# KnightOfTone.net
KiCad netlist of a schematic drawn in EAGLE
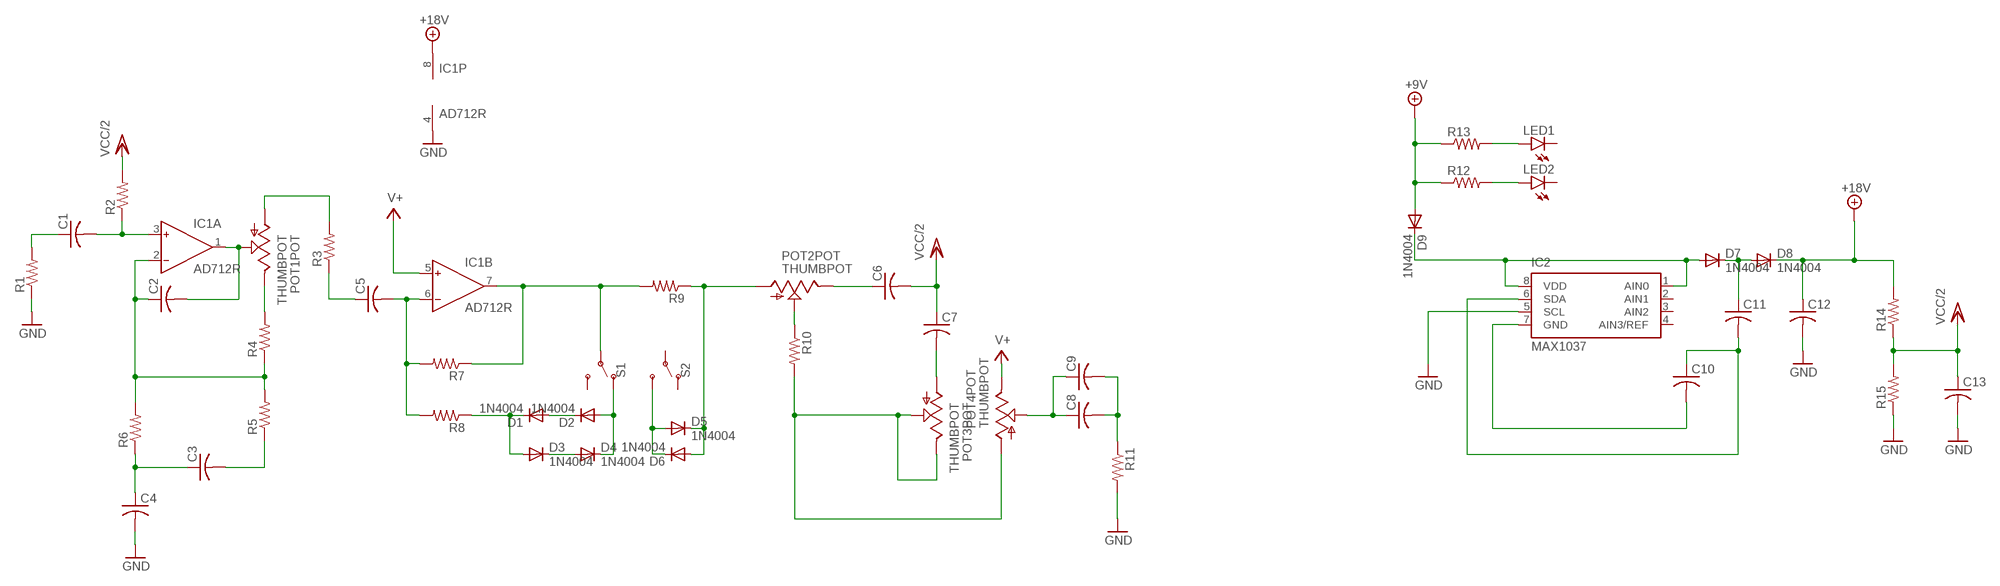
[diagram p0: schematic, sheet 1]

(export (version "E")
  (design (tool "Eeschema 10.0.6"))
  (components
    (comp (ref "C1")
      (value "C-USC0603")
      (footprint "eagle-import:C0603")
      (libsource (lib "eagle-import") (part "C-USC0603"))
    )
    (comp (ref "C2")
      (value "C-USC0603")
      (footprint "eagle-import:C0603")
      (libsource (lib "eagle-import") (part "C-USC0603"))
    )
    (comp (ref "C3")
      (value "C-USC0603")
      (footprint "eagle-import:C0603")
      (libsource (lib "eagle-import") (part "C-USC0603"))
    )
    (comp (ref "C4")
      (value "C-USC0603")
      (footprint "eagle-import:C0603")
      (libsource (lib "eagle-import") (part "C-USC0603"))
    )
    (comp (ref "C5")
      (value "C-USC0603")
      (footprint "eagle-import:C0603")
      (libsource (lib "eagle-import") (part "C-USC0603"))
    )
    (comp (ref "C6")
      (value "C-USC0603")
      (footprint "eagle-import:C0603")
      (libsource (lib "eagle-import") (part "C-USC0603"))
    )
    (comp (ref "C7")
      (value "C-USC0603")
      (footprint "eagle-import:C0603")
      (libsource (lib "eagle-import") (part "C-USC0603"))
    )
    (comp (ref "C8")
      (value "C-USC0603")
      (footprint "eagle-import:C0603")
      (libsource (lib "eagle-import") (part "C-USC0603"))
    )
    (comp (ref "C9")
      (value "C-USC0603")
      (footprint "eagle-import:C0603")
      (libsource (lib "eagle-import") (part "C-USC0603"))
    )
    (comp (ref "C10")
      (value "C-USC0603")
      (footprint "eagle-import:C0603")
      (libsource (lib "eagle-import") (part "C-USC0603"))
    )
    (comp (ref "C11")
      (value "C-USC0603")
      (footprint "eagle-import:C0603")
      (libsource (lib "eagle-import") (part "C-USC0603"))
    )
    (comp (ref "C12")
      (value "C-USC0603")
      (footprint "eagle-import:C0603")
      (libsource (lib "eagle-import") (part "C-USC0603"))
    )
    (comp (ref "C13")
      (value "C-USC0603")
      (footprint "eagle-import:C0603")
      (libsource (lib "eagle-import") (part "C-USC0603"))
    )
    (comp (ref "D1")
      (value "1N4004")
      (footprint "eagle-import:DO41-10")
      (libsource (lib "eagle-import") (part "1N4004"))
    )
    (comp (ref "D2")
      (value "1N4004")
      (footprint "eagle-import:DO41-10")
      (libsource (lib "eagle-import") (part "1N4004"))
    )
    (comp (ref "D3")
      (value "1N4004")
      (footprint "eagle-import:DO41-10")
      (libsource (lib "eagle-import") (part "1N4004"))
    )
    (comp (ref "D4")
      (value "1N4004")
      (footprint "eagle-import:DO41-10")
      (libsource (lib "eagle-import") (part "1N4004"))
    )
    (comp (ref "D5")
      (value "1N4004")
      (footprint "eagle-import:DO41-10")
      (libsource (lib "eagle-import") (part "1N4004"))
    )
    (comp (ref "D6")
      (value "1N4004")
      (footprint "eagle-import:DO41-10")
      (libsource (lib "eagle-import") (part "1N4004"))
    )
    (comp (ref "D7")
      (value "1N4004")
      (footprint "eagle-import:DO41-10")
      (libsource (lib "eagle-import") (part "1N4004"))
    )
    (comp (ref "D8")
      (value "1N4004")
      (footprint "eagle-import:DO41-10")
      (libsource (lib "eagle-import") (part "1N4004"))
    )
    (comp (ref "D9")
      (value "1N4004")
      (footprint "eagle-import:DO41-10")
      (libsource (lib "eagle-import") (part "1N4004"))
    )
    (comp (ref "IC1")
      (value "AD712R")
      (footprint "eagle-import:SO8")
      (fields (field (name "MF") "ALTERA CORPORATION") (field (name "MPN") "AD712KRZ"))
      (libsource (lib "eagle-import") (part "AD712R"))
    )
    (comp (ref "IC2")
      (value "MAX1037")
      (footprint "eagle-import:SOT23-8L")
      (fields (field (name "MF") "MAXIM") (field (name "MPN") "MAX1037EKA+T"))
      (libsource (lib "eagle-import") (part "MAX1037"))
    )
    (comp (ref "LED1")
      (value "LED3MM")
      (footprint "eagle-import:LED3MM")
      (libsource (lib "eagle-import") (part "LED3MM"))
    )
    (comp (ref "LED2")
      (value "LED3MM")
      (footprint "eagle-import:LED3MM")
      (libsource (lib "eagle-import") (part "LED3MM"))
    )
    (comp (ref "POT1")
      (value "THUMBPOT")
      (footprint "eagle-import:THUMBWHEEL")
      (libsource (lib "eagle-import") (part "THUMBPOT"))
    )
    (comp (ref "POT2")
      (value "THUMBPOT")
      (footprint "eagle-import:THUMBWHEEL")
      (libsource (lib "eagle-import") (part "THUMBPOT"))
    )
    (comp (ref "POT3")
      (value "THUMBPOT")
      (footprint "eagle-import:THUMBWHEEL")
      (libsource (lib "eagle-import") (part "THUMBPOT"))
    )
    (comp (ref "POT4")
      (value "THUMBPOT")
      (footprint "eagle-import:THUMBWHEEL")
      (libsource (lib "eagle-import") (part "THUMBPOT"))
    )
    (comp (ref "R1")
      (value "R-US_R0603")
      (footprint "eagle-import:R0603")
      (libsource (lib "eagle-import") (part "R-US_R0603"))
    )
    (comp (ref "R2")
      (value "R-US_R0603")
      (footprint "eagle-import:R0603")
      (libsource (lib "eagle-import") (part "R-US_R0603"))
    )
    (comp (ref "R3")
      (value "R-US_R0603")
      (footprint "eagle-import:R0603")
      (libsource (lib "eagle-import") (part "R-US_R0603"))
    )
    (comp (ref "R4")
      (value "R-US_R0603")
      (footprint "eagle-import:R0603")
      (libsource (lib "eagle-import") (part "R-US_R0603"))
    )
    (comp (ref "R5")
      (value "R-US_R0603")
      (footprint "eagle-import:R0603")
      (libsource (lib "eagle-import") (part "R-US_R0603"))
    )
    (comp (ref "R6")
      (value "R-US_R0603")
      (footprint "eagle-import:R0603")
      (libsource (lib "eagle-import") (part "R-US_R0603"))
    )
    (comp (ref "R7")
      (value "R-US_R0603")
      (footprint "eagle-import:R0603")
      (libsource (lib "eagle-import") (part "R-US_R0603"))
    )
    (comp (ref "R8")
      (value "R-US_R0603")
      (footprint "eagle-import:R0603")
      (libsource (lib "eagle-import") (part "R-US_R0603"))
    )
    (comp (ref "R9")
      (value "R-US_R0603")
      (footprint "eagle-import:R0603")
      (libsource (lib "eagle-import") (part "R-US_R0603"))
    )
    (comp (ref "R10")
      (value "R-US_R0603")
      (footprint "eagle-import:R0603")
      (libsource (lib "eagle-import") (part "R-US_R0603"))
    )
    (comp (ref "R11")
      (value "R-US_R0603")
      (footprint "eagle-import:R0603")
      (libsource (lib "eagle-import") (part "R-US_R0603"))
    )
    (comp (ref "R12")
      (value "R-US_R0603")
      (footprint "eagle-import:R0603")
      (libsource (lib "eagle-import") (part "R-US_R0603"))
    )
    (comp (ref "R13")
      (value "R-US_R0603")
      (footprint "eagle-import:R0603")
      (libsource (lib "eagle-import") (part "R-US_R0603"))
    )
    (comp (ref "R14")
      (value "R-US_R0603")
      (footprint "eagle-import:R0603")
      (libsource (lib "eagle-import") (part "R-US_R0603"))
    )
    (comp (ref "R15")
      (value "R-US_R0603")
      (footprint "eagle-import:R0603")
      (libsource (lib "eagle-import") (part "R-US_R0603"))
    )
    (comp (ref "S1")
      (value "SWITCH-SPDT-PTH-11.6X4.0MM")
      (footprint "eagle-import:SWITCH_SPDT_PTH_11.6X4.0MM")
      (libsource (lib "eagle-import") (part "SWITCH-SPDT-PTH-11.6X4.0MM"))
    )
    (comp (ref "S2")
      (value "SWITCH-SPDT-PTH-11.6X4.0MM")
      (footprint "eagle-import:SWITCH_SPDT_PTH_11.6X4.0MM")
      (libsource (lib "eagle-import") (part "SWITCH-SPDT-PTH-11.6X4.0MM"))
    )
  )
  (nets
    (net (code "1") (name "+9V") (class "Default")
      (node (ref "D9") (pin "A") (pinfunction "A_A") (pintype "passive"))
      (node (ref "R12") (pin "1") (pinfunction "1_1") (pintype "passive"))
      (node (ref "R13") (pin "1") (pinfunction "1_1") (pintype "passive"))
    )
    (net (code "2") (name "+18V") (class "Default")
      (node (ref "C12") (pin "1") (pinfunction "1_1") (pintype "passive"))
      (node (ref "D8") (pin "C") (pinfunction "C_C") (pintype "passive"))
      (node (ref "IC1") (pin "8") (pinfunction "V+_8") (pintype "power_in"))
      (node (ref "R14") (pin "2") (pinfunction "2_2") (pintype "passive"))
    )
    (net (code "3") (name "GND") (class "Default")
      (node (ref "C12") (pin "2") (pinfunction "2_2") (pintype "passive"))
      (node (ref "C13") (pin "2") (pinfunction "2_2") (pintype "passive"))
      (node (ref "C4") (pin "2") (pinfunction "2_2") (pintype "passive"))
      (node (ref "IC1") (pin "4") (pinfunction "V-_4") (pintype "power_in"))
      (node (ref "IC2") (pin "5") (pinfunction "SCL_5") (pintype "input"))
      (node (ref "R1") (pin "1") (pinfunction "1_1") (pintype "passive"))
      (node (ref "R11") (pin "2") (pinfunction "2_2") (pintype "passive"))
      (node (ref "R15") (pin "1") (pinfunction "1_1") (pintype "passive"))
    )
    (net (code "4") (name "Net-(C1-Pad1)") (class "Default")
      (node (ref "C1") (pin "1") (pinfunction "1_1") (pintype "passive"))
      (node (ref "R1") (pin "2") (pinfunction "2_2") (pintype "passive"))
    )
    (net (code "5") (name "Net-(C3-Pad1)") (class "Default")
      (node (ref "C3") (pin "1") (pinfunction "1_1") (pintype "passive"))
      (node (ref "C4") (pin "1") (pinfunction "1_1") (pintype "passive"))
      (node (ref "R6") (pin "1") (pinfunction "1_1") (pintype "passive"))
    )
    (net (code "6") (name "Net-(C3-Pad2)") (class "Default")
      (node (ref "C3") (pin "2") (pinfunction "2_2") (pintype "passive"))
      (node (ref "R5") (pin "1") (pinfunction "1_1") (pintype "passive"))
    )
    (net (code "7") (name "Net-(C5-Pad1)") (class "Default")
      (node (ref "C5") (pin "1") (pinfunction "1_1") (pintype "passive"))
      (node (ref "R3") (pin "1") (pinfunction "1_1") (pintype "passive"))
    )
    (net (code "8") (name "Net-(C8-Pad2)") (class "Default")
      (node (ref "C8") (pin "2") (pinfunction "2_2") (pintype "passive"))
      (node (ref "C9") (pin "2") (pinfunction "2_2") (pintype "passive"))
      (node (ref "R11") (pin "1") (pinfunction "1_1") (pintype "passive"))
    )
    (net (code "9") (name "Net-(C11-Pad1)") (class "Default")
      (node (ref "C11") (pin "1") (pinfunction "1_1") (pintype "passive"))
      (node (ref "D7") (pin "C") (pinfunction "C_C") (pintype "passive"))
      (node (ref "D8") (pin "A") (pinfunction "A_A") (pintype "passive"))
    )
    (net (code "10") (name "Net-(D1-PadA)") (class "Default")
      (node (ref "D1") (pin "A") (pinfunction "A_A") (pintype "passive"))
      (node (ref "D2") (pin "C") (pinfunction "C_C") (pintype "passive"))
    )
    (net (code "11") (name "Net-(D1-PadC)") (class "Default")
      (node (ref "D1") (pin "C") (pinfunction "C_C") (pintype "passive"))
      (node (ref "D3") (pin "A") (pinfunction "A_A") (pintype "passive"))
      (node (ref "R8") (pin "1") (pinfunction "1_1") (pintype "passive"))
    )
    (net (code "12") (name "Net-(D3-PadC)") (class "Default")
      (node (ref "D3") (pin "C") (pinfunction "C_C") (pintype "passive"))
      (node (ref "D4") (pin "A") (pinfunction "A_A") (pintype "passive"))
    )
    (net (code "13") (name "Net-(IC1A-IN+)") (class "Default")
      (node (ref "C1") (pin "2") (pinfunction "2_2") (pintype "passive"))
      (node (ref "IC1") (pin "3") (pinfunction "IN+_3") (pintype "input"))
      (node (ref "R2") (pin "1") (pinfunction "1_1") (pintype "passive"))
    )
    (net (code "14") (name "Net-(IC1A-IN-)") (class "Default")
      (node (ref "C2") (pin "1") (pinfunction "1_1") (pintype "passive"))
      (node (ref "IC1") (pin "2") (pinfunction "IN-_2") (pintype "input"))
      (node (ref "R4") (pin "1") (pinfunction "1_1") (pintype "passive"))
      (node (ref "R5") (pin "2") (pinfunction "2_2") (pintype "passive"))
      (node (ref "R6") (pin "2") (pinfunction "2_2") (pintype "passive"))
    )
    (net (code "15") (name "Net-(IC1A-OUT)") (class "Default")
      (node (ref "C2") (pin "2") (pinfunction "2_2") (pintype "passive"))
      (node (ref "IC1") (pin "1") (pinfunction "OUT_1") (pintype "output"))
      (node (ref "POT1") (pin "2") (pinfunction "S_2") (pintype "passive"))
    )
    (net (code "16") (name "Net-(IC1B-IN-)") (class "Default")
      (node (ref "C5") (pin "2") (pinfunction "2_2") (pintype "passive"))
      (node (ref "IC1") (pin "6") (pinfunction "IN-_6") (pintype "input"))
      (node (ref "R7") (pin "2") (pinfunction "2_2") (pintype "passive"))
      (node (ref "R8") (pin "2") (pinfunction "2_2") (pintype "passive"))
    )
    (net (code "17") (name "Net-(IC1B-OUT)") (class "Default")
      (node (ref "IC1") (pin "7") (pinfunction "OUT_7") (pintype "output"))
      (node (ref "R7") (pin "1") (pinfunction "1_1") (pintype "passive"))
      (node (ref "R9") (pin "2") (pinfunction "2_2") (pintype "passive"))
      (node (ref "S1") (pin "2") (pinfunction "P_2") (pintype "passive"))
    )
    (net (code "18") (name "Net-(IC2-AIN0)") (class "Default")
      (node (ref "D7") (pin "A") (pinfunction "A_A") (pintype "passive"))
      (node (ref "D9") (pin "C") (pinfunction "C_C") (pintype "passive"))
      (node (ref "IC2") (pin "1") (pinfunction "AIN0_1") (pintype "input"))
      (node (ref "IC2") (pin "8") (pinfunction "VDD_8") (pintype "power_in"))
    )
    (net (code "19") (name "Net-(IC2-GND)") (class "Default")
      (node (ref "C10") (pin "2") (pinfunction "2_2") (pintype "passive"))
      (node (ref "IC2") (pin "7") (pinfunction "GND_7") (pintype "power_in"))
    )
    (net (code "20") (name "Net-(IC2-SDA)") (class "Default")
      (node (ref "C10") (pin "1") (pinfunction "1_1") (pintype "passive"))
      (node (ref "C11") (pin "2") (pinfunction "2_2") (pintype "passive"))
      (node (ref "IC2") (pin "6") (pinfunction "SDA_6") (pintype "input"))
    )
    (net (code "21") (name "Net-(LED1-PadA)") (class "Default")
      (node (ref "LED1") (pin "A") (pinfunction "A_A") (pintype "passive"))
      (node (ref "R13") (pin "2") (pinfunction "2_2") (pintype "passive"))
    )
    (net (code "22") (name "Net-(LED2-PadA)") (class "Default")
      (node (ref "LED2") (pin "A") (pinfunction "A_A") (pintype "passive"))
      (node (ref "R12") (pin "2") (pinfunction "2_2") (pintype "passive"))
    )
    (net (code "23") (name "Net-(POT1A-A)") (class "Default")
      (node (ref "POT1") (pin "1") (pinfunction "A_1") (pintype "passive"))
      (node (ref "R3") (pin "2") (pinfunction "2_2") (pintype "passive"))
    )
    (net (code "24") (name "Net-(POT1A-E)") (class "Default")
      (node (ref "POT1") (pin "3") (pinfunction "E_3") (pintype "passive"))
      (node (ref "R4") (pin "2") (pinfunction "2_2") (pintype "passive"))
    )
    (net (code "25") (name "Net-(POT2A-A)") (class "Default")
      (node (ref "D5") (pin "C") (pinfunction "C_C") (pintype "passive"))
      (node (ref "D6") (pin "A") (pinfunction "A_A") (pintype "passive"))
      (node (ref "POT2") (pin "1") (pinfunction "A_1") (pintype "passive"))
      (node (ref "R9") (pin "1") (pinfunction "1_1") (pintype "passive"))
    )
    (net (code "26") (name "Net-(POT2A-E)") (class "Default")
      (node (ref "C6") (pin "1") (pinfunction "1_1") (pintype "passive"))
      (node (ref "POT2") (pin "3") (pinfunction "E_3") (pintype "passive"))
    )
    (net (code "27") (name "Net-(POT2A-S)") (class "Default")
      (node (ref "POT2") (pin "2") (pinfunction "S_2") (pintype "passive"))
      (node (ref "R10") (pin "1") (pinfunction "1_1") (pintype "passive"))
    )
    (net (code "28") (name "Net-(POT3A-A)") (class "Default")
      (node (ref "C7") (pin "2") (pinfunction "2_2") (pintype "passive"))
      (node (ref "POT3") (pin "1") (pinfunction "A_1") (pintype "passive"))
    )
    (net (code "29") (name "Net-(POT3A-E)") (class "Default")
      (node (ref "POT3") (pin "2") (pinfunction "S_2") (pintype "passive"))
      (node (ref "POT3") (pin "3") (pinfunction "E_3") (pintype "passive"))
      (node (ref "POT4") (pin "1") (pinfunction "A_1") (pintype "passive"))
      (node (ref "R10") (pin "2") (pinfunction "2_2") (pintype "passive"))
    )
    (net (code "30") (name "Net-(POT4A-S)") (class "Default")
      (node (ref "C8") (pin "1") (pinfunction "1_1") (pintype "passive"))
      (node (ref "C9") (pin "1") (pinfunction "1_1") (pintype "passive"))
      (node (ref "POT4") (pin "2") (pinfunction "S_2") (pintype "passive"))
    )
    (net (code "31") (name "Net-(S1-O)") (class "Default")
      (node (ref "D2") (pin "A") (pinfunction "A_A") (pintype "passive"))
      (node (ref "D4") (pin "C") (pinfunction "C_C") (pintype "passive"))
      (node (ref "S1") (pin "1") (pinfunction "O_1") (pintype "passive"))
    )
    (net (code "32") (name "Net-(S2-S)") (class "Default")
      (node (ref "D5") (pin "A") (pinfunction "A_A") (pintype "passive"))
      (node (ref "D6") (pin "C") (pinfunction "C_C") (pintype "passive"))
      (node (ref "S2") (pin "3") (pinfunction "S_3") (pintype "passive"))
    )
    (net (code "33") (name "V+") (class "Default")
      (node (ref "IC1") (pin "5") (pinfunction "IN+_5") (pintype "input"))
      (node (ref "POT4") (pin "3") (pinfunction "E_3") (pintype "passive"))
    )
    (net (code "34") (name "VCC{slash}2") (class "Default")
      (node (ref "C13") (pin "1") (pinfunction "1_1") (pintype "passive"))
      (node (ref "C6") (pin "2") (pinfunction "2_2") (pintype "passive"))
      (node (ref "C7") (pin "1") (pinfunction "1_1") (pintype "passive"))
      (node (ref "R14") (pin "1") (pinfunction "1_1") (pintype "passive"))
      (node (ref "R15") (pin "2") (pinfunction "2_2") (pintype "passive"))
      (node (ref "R2") (pin "2") (pinfunction "2_2") (pintype "passive"))
    )
    (net (code "35") (name "unconnected-(IC2-AIN1-Pad2)") (class "Default")
      (node (ref "IC2") (pin "2") (pinfunction "AIN1_2") (pintype "input"))
    )
    (net (code "36") (name "unconnected-(IC2-AIN2-Pad3)") (class "Default")
      (node (ref "IC2") (pin "3") (pinfunction "AIN2_3") (pintype "input"))
    )
    (net (code "37") (name "unconnected-(IC2-AIN3{slash}REF-Pad4)") (class "Default")
      (node (ref "IC2") (pin "4") (pinfunction "AIN3/REF_4") (pintype "input"))
    )
    (net (code "38") (name "unconnected-(LED1-C-PadK)") (class "Default")
      (node (ref "LED1") (pin "K") (pinfunction "C_K") (pintype "passive"))
    )
    (net (code "39") (name "unconnected-(LED2-C-PadK)") (class "Default")
      (node (ref "LED2") (pin "K") (pinfunction "C_K") (pintype "passive"))
    )
    (net (code "40") (name "unconnected-(S1-S-Pad3)") (class "Default")
      (node (ref "S1") (pin "3") (pinfunction "S_3") (pintype "passive"))
    )
    (net (code "41") (name "unconnected-(S2-O-Pad1)") (class "Default")
      (node (ref "S2") (pin "1") (pinfunction "O_1") (pintype "passive"))
    )
    (net (code "42") (name "unconnected-(S2-P-Pad2)") (class "Default")
      (node (ref "S2") (pin "2") (pinfunction "P_2") (pintype "passive"))
    )
  )
)
